# 7_-_ADC_Chip.net
KiCad netlist of a schematic drawn in Altium Designer
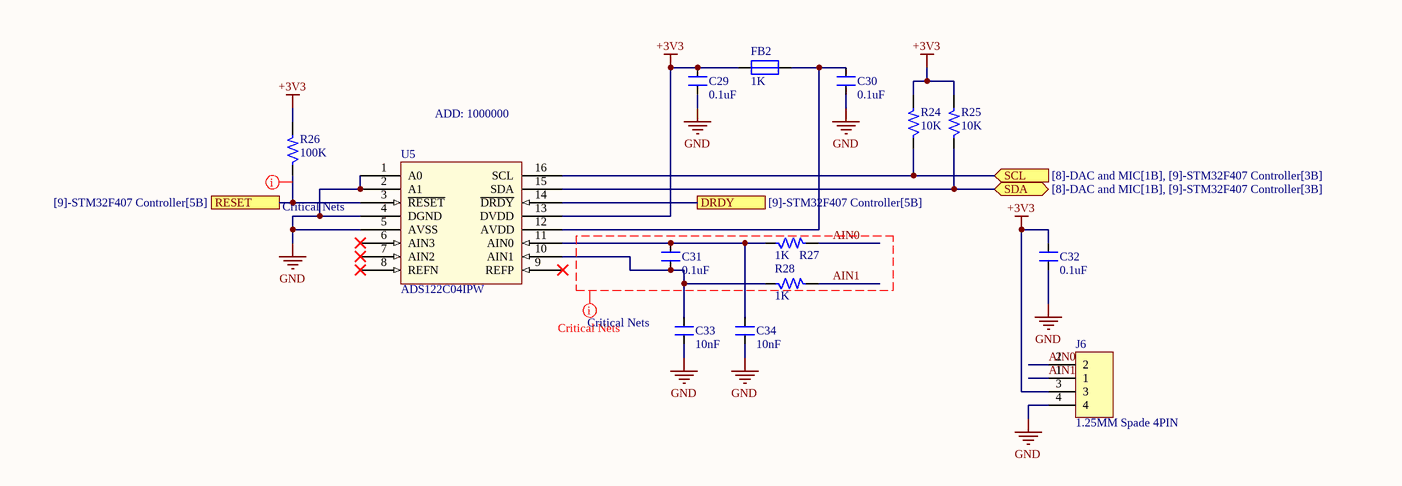
[diagram p0: [7]- ADC Chip.SchDoc]

(export (version "E")
  (design (tool "Eeschema 10.0.6"))
  (components
    (comp (ref "C29")
      (value "0.1uF")
      (footprint "CAP_0805")
      (description "0.1µF ±10% 50V Ceramic Capacitor X7R 0805 (2012 Metric)")
      (fields
        (field (name "MANUFACTURER") "Samsung")
        (field (name "MANUFACTURER PART NUMBER") "CL21B104KBCNNNC")
      )
      (libsource (lib "ESTEEMPCBLIB") (part "CAP_0.1uF-50V-10%-0805"))
    )
    (comp (ref "C30")
      (value "0.1uF")
      (footprint "CAP_0805")
      (description "0.1µF ±10% 50V Ceramic Capacitor X7R 0805 (2012 Metric)")
      (fields
        (field (name "MANUFACTURER") "Samsung")
        (field (name "MANUFACTURER PART NUMBER") "CL21B104KBCNNNC")
      )
      (libsource (lib "ESTEEMPCBLIB") (part "CAP_0.1uF-50V-10%-0805"))
    )
    (comp (ref "C31")
      (value "0.1uF")
      (footprint "CAP_0805")
      (description "0.1µF ±10% 50V Ceramic Capacitor X7R 0805 (2012 Metric)")
      (fields
        (field (name "MANUFACTURER") "Samsung")
        (field (name "MANUFACTURER PART NUMBER") "CL21B104KBCNNNC")
      )
      (libsource (lib "ESTEEMPCBLIB") (part "CAP_0.1uF-50V-10%-0805"))
    )
    (comp (ref "C32")
      (value "0.1uF")
      (footprint "CAP_0805")
      (description "0.1µF ±10% 50V Ceramic Capacitor X7R 0805 (2012 Metric)")
      (fields
        (field (name "MANUFACTURER") "Samsung")
        (field (name "MANUFACTURER PART NUMBER") "CL21B104KBCNNNC")
      )
      (libsource (lib "ESTEEMPCBLIB") (part "CAP_0.1uF-50V-10%-0805"))
    )
    (comp (ref "C33")
      (value "10nF")
      (footprint "CAP_0805")
      (description "10000pF ±10% 50V Ceramic Capacitor X7R 0805 (2012 Metric)")
      (fields
        (field (name "MANUFACTURER") "Samsung")
        (field (name "MANUFACTURER PART NUMBER") "C0805C103K5RECAUTO")
      )
      (libsource (lib "ESTEEMPCBLIB") (part "CAP_10nF-50V-10%-0805"))
    )
    (comp (ref "C34")
      (value "10nF")
      (footprint "CAP_0805")
      (description "10000pF ±10% 50V Ceramic Capacitor X7R 0805 (2012 Metric)")
      (fields
        (field (name "MANUFACTURER") "Samsung")
        (field (name "MANUFACTURER PART NUMBER") "C0805C103K5RECAUTO")
      )
      (libsource (lib "ESTEEMPCBLIB") (part "CAP_10nF-50V-10%-0805"))
    )
    (comp (ref "FB2")
      (value "1K")
      (footprint "IND_0805")
      (description "1 kOhms @ 100MHz 1 Power Line Ferrite Bead 0805 (2012 Metric) 1.6A")
      (fields
        (field (name "MANUFACTURER") "Laird")
        (field (name "MANUFACTURER PART NUMBER") "BLM21SP102SH1D")
      )
      (libsource (lib "ESTEEMPCBLIB") (part "FB_1K-100MHZ-1.6A-0805"))
    )
    (comp (ref "J6")
      (value "1.25MM Spade 4PIN")
      (footprint "CON4_50_653004117322_TH_RA")
      (description "4 Pins, 1 Row 1.25mm Pitch, right angle Connector, male")
      (fields (field (name "MANUFACTURER PART NUMBER") "653004117322") (field (name "MANUFACTURER") "JST"))
      (libsource (lib "ESTEEMPCBLIB") (part "CON-PLG_4X1-50-RA-TH"))
    )
    (comp (ref "R24")
      (value "10K")
      (footprint "RES_0603")
      (description "10 kOhms ±1% 0.1W, 1/10W Chip Resistor 0603 (1608 Metric) Automotive AEC-Q200 Thick Film")
      (fields (field (name "MANUFACTURER") "Walsin") (field (name "MANUFACTURER PART NUMBER") "WR06X1002FTL"))
      (libsource (lib "ESTEEMPCBLIB") (part "RES_10K-0.1W-1%-0603"))
    )
    (comp (ref "R25")
      (value "10K")
      (footprint "RES_0603")
      (description "10 kOhms ±1% 0.1W, 1/10W Chip Resistor 0603 (1608 Metric) Automotive AEC-Q200 Thick Film")
      (fields (field (name "MANUFACTURER") "Walsin") (field (name "MANUFACTURER PART NUMBER") "WR06X1002FTL"))
      (libsource (lib "ESTEEMPCBLIB") (part "RES_10K-0.1W-1%-0603"))
    )
    (comp (ref "R26")
      (value "100K")
      (footprint "RES_0603")
      (description "100 kOhms ±1% 0.1W, 1/10W Chip Resistor 0603 (1608 Metric) Automotive AEC-Q200 Thick Film")
      (fields
        (field (name "MANUFACTURER") "Stackpole Electronics")
        (field (name "MANUFACTURER PART NUMBER") "RMCF0603FT100K")
      )
      (libsource (lib "ESTEEMPCBLIB") (part "RES_100K-0.1W-1%-0603"))
    )
    (comp (ref "R27")
      (value "1K")
      (footprint "RES_0603")
      (description "1 kOhms ±1% 0.1W, 1/10W Chip Resistor 0603 (1608 Metric) Automotive AEC-Q200 Thick Film")
      (fields (field (name "MANUFACTURER") "Walsin") (field (name "MANUFACTURER PART NUMBER") "WR06X1001FTL"))
      (libsource (lib "ESTEEMPCBLIB") (part "RES_1K-0.1W-1%-0603"))
    )
    (comp (ref "R28")
      (value "1K")
      (footprint "RES_0603")
      (description "1 kOhms ±1% 0.1W, 1/10W Chip Resistor 0603 (1608 Metric) Automotive AEC-Q200 Thick Film")
      (fields (field (name "MANUFACTURER") "Walsin") (field (name "MANUFACTURER PART NUMBER") "WR06X1001FTL"))
      (libsource (lib "ESTEEMPCBLIB") (part "RES_1K-0.1W-1%-0603"))
    )
    (comp (ref "U5")
      (value "ADS122C04IPW")
      (footprint "TSSOP16_25-59_294_54X14_SMT")
      (description "24 Bit Analog to Digital Converter 4 Input 1 Sigma-Delta 16-TSSOP")
      (fields (field (name "MANUFACTURER") "Texas Instruments"))
      (libsource (lib "ESTEEMPCBLIB") (part "IC_ADS122C04IPW"))
    )
  )
  (nets
    (net (code "1") (name "+3V3") (class "Default")
      (node (ref "C29") (pin "2") (pinfunction "2_2") (pintype "passive"))
      (node (ref "C32") (pin "2") (pinfunction "2_2") (pintype "passive"))
      (node (ref "FB2") (pin "1") (pinfunction "1_1") (pintype "passive"))
      (node (ref "J6") (pin "3") (pinfunction "3_3") (pintype "passive"))
      (node (ref "R24") (pin "2") (pinfunction "2_2") (pintype "passive"))
      (node (ref "R25") (pin "2") (pinfunction "2_2") (pintype "passive"))
      (node (ref "R26") (pin "2") (pinfunction "2_2") (pintype "passive"))
      (node (ref "U5") (pin "13") (pinfunction "DVDD_13") (pintype "power_in"))
    )
    (net (code "2") (name "/AIN0") (class "Default")
      (node (ref "J6") (pin "2") (pinfunction "2_2") (pintype "passive"))
      (node (ref "R27") (pin "2") (pinfunction "2_2") (pintype "passive"))
    )
    (net (code "3") (name "/AIN1") (class "Default")
      (node (ref "J6") (pin "1") (pinfunction "1_1") (pintype "passive"))
      (node (ref "R28") (pin "2") (pinfunction "2_2") (pintype "passive"))
    )
    (net (code "4") (name "/DRDY") (class "Default")
      (node (ref "U5") (pin "14") (pinfunction "DRDY_14") (pintype "input"))
    )
    (net (code "5") (name "/RESET") (class "Default")
      (node (ref "R26") (pin "1") (pinfunction "1_1") (pintype "passive"))
      (node (ref "U5") (pin "3") (pinfunction "RESET_3") (pintype "input"))
    )
    (net (code "6") (name "/SCL") (class "Default")
      (node (ref "R24") (pin "1") (pinfunction "1_1") (pintype "passive"))
      (node (ref "U5") (pin "16") (pinfunction "SCL_16") (pintype "open_collector"))
    )
    (net (code "7") (name "/SDA") (class "Default")
      (node (ref "R25") (pin "1") (pinfunction "1_1") (pintype "passive"))
      (node (ref "U5") (pin "15") (pinfunction "SDA_15") (pintype "open_collector"))
    )
    (net (code "8") (name "GND") (class "Default")
      (node (ref "C29") (pin "1") (pinfunction "1_1") (pintype "passive"))
      (node (ref "C30") (pin "1") (pinfunction "1_1") (pintype "passive"))
      (node (ref "C32") (pin "1") (pinfunction "1_1") (pintype "passive"))
      (node (ref "C33") (pin "1") (pinfunction "1_1") (pintype "passive"))
      (node (ref "C34") (pin "1") (pinfunction "1_1") (pintype "passive"))
      (node (ref "J6") (pin "4") (pinfunction "4_4") (pintype "passive"))
      (node (ref "U5") (pin "1") (pinfunction "A0_1") (pintype "passive"))
      (node (ref "U5") (pin "2") (pinfunction "A1_2") (pintype "passive"))
      (node (ref "U5") (pin "4") (pinfunction "DGND_4") (pintype "power_in"))
      (node (ref "U5") (pin "5") (pinfunction "AVSS_5") (pintype "power_in"))
    )
    (net (code "9") (name "Net-(U5-AIN0)") (class "Default")
      (node (ref "C31") (pin "2") (pinfunction "2_2") (pintype "passive"))
      (node (ref "C34") (pin "2") (pinfunction "2_2") (pintype "passive"))
      (node (ref "R27") (pin "1") (pinfunction "1_1") (pintype "passive"))
      (node (ref "U5") (pin "11") (pinfunction "AIN0_11") (pintype "input"))
    )
    (net (code "10") (name "Net-(U5-AIN1)") (class "Default")
      (node (ref "C31") (pin "1") (pinfunction "1_1") (pintype "passive"))
      (node (ref "C33") (pin "2") (pinfunction "2_2") (pintype "passive"))
      (node (ref "R28") (pin "1") (pinfunction "1_1") (pintype "passive"))
      (node (ref "U5") (pin "10") (pinfunction "AIN1_10") (pintype "input"))
    )
    (net (code "11") (name "Net-(U5-AVDD)") (class "Default")
      (node (ref "C30") (pin "2") (pinfunction "2_2") (pintype "passive"))
      (node (ref "FB2") (pin "2") (pinfunction "2_2") (pintype "passive"))
      (node (ref "U5") (pin "12") (pinfunction "AVDD_12") (pintype "power_in"))
    )
    (net (code "12") (name "unconnected-(U5-AIN2-Pad7)") (class "Default")
      (node (ref "U5") (pin "7") (pinfunction "AIN2_7") (pintype "input+no_connect"))
    )
    (net (code "13") (name "unconnected-(U5-AIN3-Pad6)") (class "Default")
      (node (ref "U5") (pin "6") (pinfunction "AIN3_6") (pintype "input+no_connect"))
    )
    (net (code "14") (name "unconnected-(U5-REFN-Pad8)") (class "Default")
      (node (ref "U5") (pin "8") (pinfunction "REFN_8") (pintype "input+no_connect"))
    )
    (net (code "15") (name "unconnected-(U5-REFP-Pad9)") (class "Default")
      (node (ref "U5") (pin "9") (pinfunction "REFP_9") (pintype "input+no_connect"))
    )
  )
)
